# Versa64Cart_v1_5.net
KiCad netlist of a schematic drawn in EAGLE
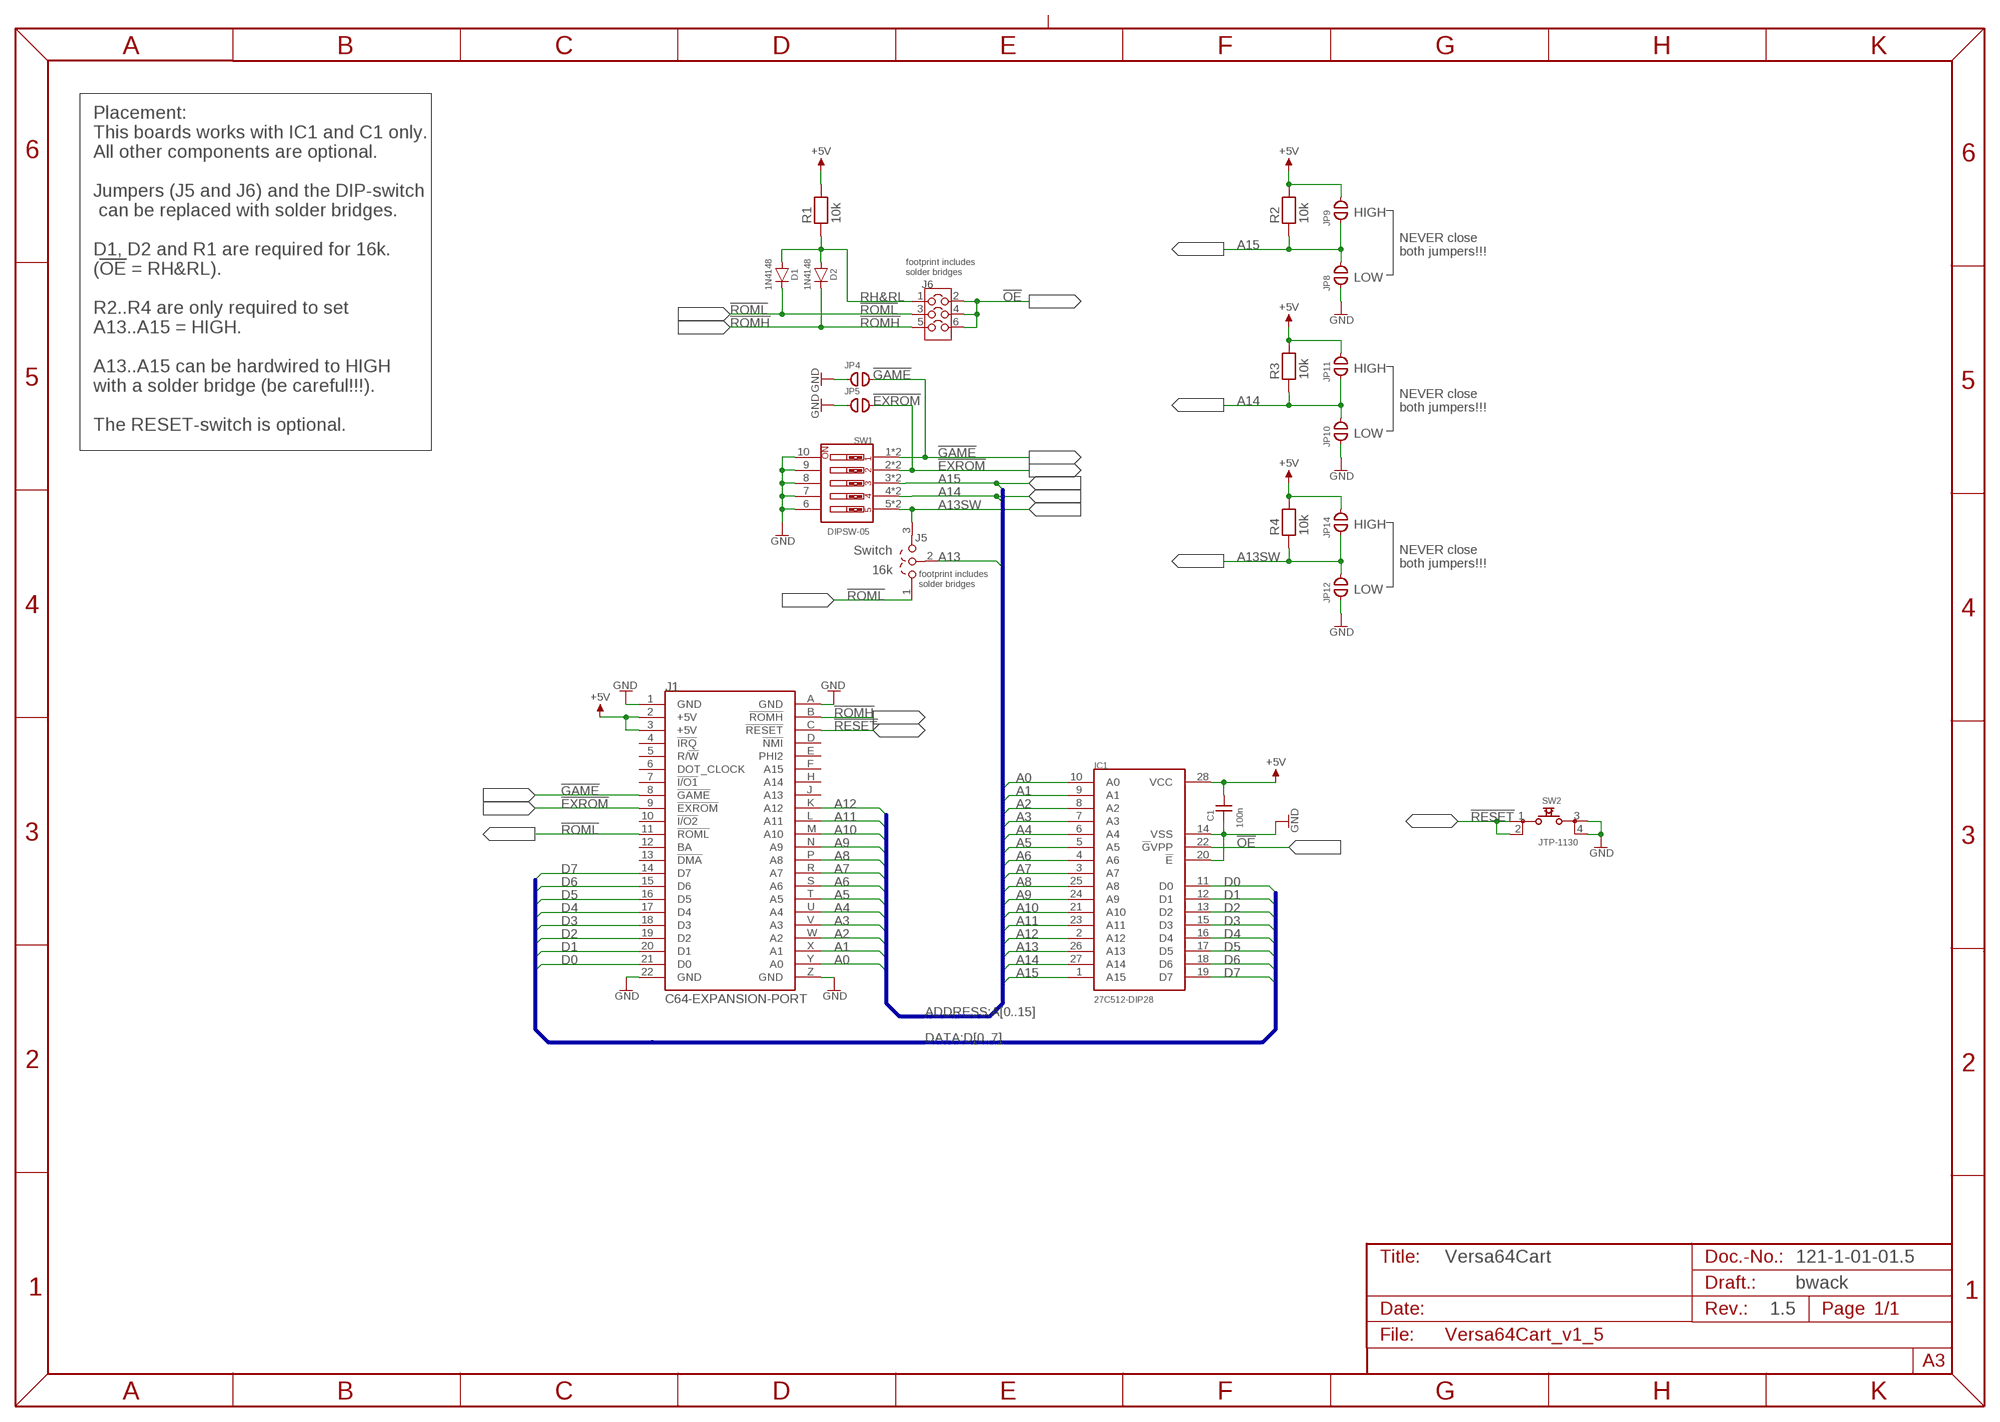
[diagram p0: schematic, sheet 1]

(export (version "E")
  (design (tool "Eeschema 10.0.6"))
  (components
    (comp (ref "C1")
      (value "100n")
      (footprint "eagle-import:C-2,5")
      (libsource (lib "eagle-import") (part "CAP01"))
    )
    (comp (ref "D1")
      (value "1N4148")
      (footprint "eagle-import:DO-35")
      (libsource (lib "eagle-import") (part "1N4148"))
    )
    (comp (ref "D2")
      (value "1N4148")
      (footprint "eagle-import:DO-35")
      (libsource (lib "eagle-import") (part "1N4148"))
    )
    (comp (ref "IC1")
      (value "27C512-DIP28")
      (footprint "eagle-import:DIL28-6")
      (libsource (lib "eagle-import") (part "M27C512-DIP28"))
    )
    (comp (ref "J1")
      (value "C64-EXPANSION-PORT")
      (footprint "eagle-import:EXPANSIO_SQ")
      (libsource (lib "eagle-import") (part "C64-EXPANSIONPNARROW"))
    )
    (comp (ref "J5")
      (value "COMBI-3P")
      (footprint "eagle-import:COMBI-3P")
      (libsource (lib "eagle-import") (part "COMBI-3P"))
    )
    (comp (ref "J6")
      (value "COMBI-3X2P")
      (footprint "eagle-import:COMBI-3X2")
      (fields (field (name "SPICEPREFIX") "X"))
      (libsource (lib "eagle-import") (part "COMBI-3X2P"))
    )
    (comp (ref "JP4")
      (value "OPEN")
      (footprint "eagle-import:CP_OP")
      (libsource (lib "eagle-import") (part "OPEN"))
    )
    (comp (ref "JP5")
      (value "OPEN")
      (footprint "eagle-import:CP_OP")
      (libsource (lib "eagle-import") (part "OPEN"))
    )
    (comp (ref "JP8")
      (value "OPEN")
      (footprint "eagle-import:CP_OP")
      (libsource (lib "eagle-import") (part "OPEN"))
    )
    (comp (ref "JP9")
      (value "OPEN")
      (footprint "eagle-import:CP_OP")
      (libsource (lib "eagle-import") (part "OPEN"))
    )
    (comp (ref "JP10")
      (value "OPEN")
      (footprint "eagle-import:CP_OP")
      (libsource (lib "eagle-import") (part "OPEN"))
    )
    (comp (ref "JP11")
      (value "OPEN")
      (footprint "eagle-import:CP_OP")
      (libsource (lib "eagle-import") (part "OPEN"))
    )
    (comp (ref "JP12")
      (value "OPEN")
      (footprint "eagle-import:CP_OP")
      (libsource (lib "eagle-import") (part "OPEN"))
    )
    (comp (ref "JP14")
      (value "OPEN")
      (footprint "eagle-import:CP_OP")
      (libsource (lib "eagle-import") (part "OPEN"))
    )
    (comp (ref "R1")
      (value "10k")
      (footprint "eagle-import:R-10")
      (libsource (lib "eagle-import") (part "RES04"))
    )
    (comp (ref "R2")
      (value "10k")
      (footprint "eagle-import:R-10")
      (libsource (lib "eagle-import") (part "RES04"))
    )
    (comp (ref "R3")
      (value "10k")
      (footprint "eagle-import:R-10")
      (libsource (lib "eagle-import") (part "RES04"))
    )
    (comp (ref "R4")
      (value "10k")
      (footprint "eagle-import:R-10")
      (libsource (lib "eagle-import") (part "RES04"))
    )
    (comp (ref "SW1")
      (value "DIPSW-05")
      (footprint "eagle-import:DIPSW-05VJ")
      (libsource (lib "eagle-import") (part "DIPSW-05"))
    )
    (comp (ref "SW2")
      (value "JTP-1130")
      (footprint "eagle-import:JTP-1130")
      (libsource (lib "eagle-import") (part "JTP-1130"))
    )
  )
  (nets
    (net (code "25") (name "+5V") (class "Default")
      (node (ref "C1") (pin "2") (pinfunction "2_2") (pintype "passive"))
      (node (ref "IC1") (pin "28") (pinfunction "VCC_28") (pintype "power_in"))
      (node (ref "J1") (pin "2") (pinfunction "+5V_2") (pintype "power_in"))
      (node (ref "J1") (pin "3") (pinfunction "+5V_3") (pintype "power_in"))
      (node (ref "JP11") (pin "2") (pinfunction "2_2") (pintype "passive"))
      (node (ref "JP14") (pin "2") (pinfunction "2_2") (pintype "passive"))
      (node (ref "JP9") (pin "2") (pinfunction "2_2") (pintype "passive"))
      (node (ref "R1") (pin "2") (pinfunction "2_2") (pintype "passive"))
      (node (ref "R2") (pin "2") (pinfunction "2_2") (pintype "passive"))
      (node (ref "R3") (pin "2") (pinfunction "2_2") (pintype "passive"))
      (node (ref "R4") (pin "2") (pinfunction "2_2") (pintype "passive"))
    )
    (net (code "26") (name "/A0") (class "Default")
      (node (ref "IC1") (pin "10") (pinfunction "A0_10") (pintype "input"))
      (node (ref "J1") (pin "Y") (pinfunction "A0_Y") (pintype "bidirectional"))
    )
    (net (code "27") (name "/A1") (class "Default")
      (node (ref "IC1") (pin "9") (pinfunction "A1_9") (pintype "input"))
      (node (ref "J1") (pin "X") (pinfunction "A1_X") (pintype "bidirectional"))
    )
    (net (code "28") (name "/A2") (class "Default")
      (node (ref "IC1") (pin "8") (pinfunction "A2_8") (pintype "input"))
      (node (ref "J1") (pin "W") (pinfunction "A2_W") (pintype "bidirectional"))
    )
    (net (code "29") (name "/A3") (class "Default")
      (node (ref "IC1") (pin "7") (pinfunction "A3_7") (pintype "input"))
      (node (ref "J1") (pin "V") (pinfunction "A3_V") (pintype "bidirectional"))
    )
    (net (code "30") (name "/A4") (class "Default")
      (node (ref "IC1") (pin "6") (pinfunction "A4_6") (pintype "input"))
      (node (ref "J1") (pin "U") (pinfunction "A4_U") (pintype "bidirectional"))
    )
    (net (code "31") (name "/A5") (class "Default")
      (node (ref "IC1") (pin "5") (pinfunction "A5_5") (pintype "input"))
      (node (ref "J1") (pin "T") (pinfunction "A5_T") (pintype "bidirectional"))
    )
    (net (code "32") (name "/A6") (class "Default")
      (node (ref "IC1") (pin "4") (pinfunction "A6_4") (pintype "input"))
      (node (ref "J1") (pin "S") (pinfunction "A6_S") (pintype "bidirectional"))
    )
    (net (code "33") (name "/A7") (class "Default")
      (node (ref "IC1") (pin "3") (pinfunction "A7_3") (pintype "input"))
      (node (ref "J1") (pin "R") (pinfunction "A7_R") (pintype "bidirectional"))
    )
    (net (code "34") (name "/A8") (class "Default")
      (node (ref "IC1") (pin "25") (pinfunction "A8_25") (pintype "input"))
      (node (ref "J1") (pin "P") (pinfunction "A8_P") (pintype "bidirectional"))
    )
    (net (code "35") (name "/A9") (class "Default")
      (node (ref "IC1") (pin "24") (pinfunction "A9_24") (pintype "input"))
      (node (ref "J1") (pin "N") (pinfunction "A9_N") (pintype "bidirectional"))
    )
    (net (code "36") (name "/A10") (class "Default")
      (node (ref "IC1") (pin "21") (pinfunction "A10_21") (pintype "input"))
      (node (ref "J1") (pin "M") (pinfunction "A10_M") (pintype "bidirectional"))
    )
    (net (code "37") (name "/A11") (class "Default")
      (node (ref "IC1") (pin "23") (pinfunction "A11_23") (pintype "input"))
      (node (ref "J1") (pin "L") (pinfunction "A11_L") (pintype "bidirectional"))
    )
    (net (code "38") (name "/A12") (class "Default")
      (node (ref "IC1") (pin "2") (pinfunction "A12_2") (pintype "input"))
      (node (ref "J1") (pin "K") (pinfunction "A12_K") (pintype "bidirectional"))
    )
    (net (code "39") (name "/A13") (class "Default")
      (node (ref "IC1") (pin "26") (pinfunction "A13_26") (pintype "input"))
      (node (ref "J5") (pin "2") (pinfunction "2_2") (pintype "bidirectional"))
    )
    (net (code "40") (name "/A13SW") (class "Default")
      (node (ref "J5") (pin "3") (pinfunction "3_3") (pintype "bidirectional"))
      (node (ref "JP12") (pin "2") (pinfunction "2_2") (pintype "passive"))
      (node (ref "JP14") (pin "1") (pinfunction "1_1") (pintype "passive"))
      (node (ref "R4") (pin "1") (pinfunction "1_1") (pintype "passive"))
      (node (ref "SW1") (pin "5") (pinfunction "5_5") (pintype "passive"))
      (node (ref "SW1") (pin "5J") (pinfunction "5_5J") (pintype "passive"))
    )
    (net (code "41") (name "/A14") (class "Default")
      (node (ref "IC1") (pin "27") (pinfunction "A14_27") (pintype "input"))
      (node (ref "JP10") (pin "2") (pinfunction "2_2") (pintype "passive"))
      (node (ref "JP11") (pin "1") (pinfunction "1_1") (pintype "passive"))
      (node (ref "R3") (pin "1") (pinfunction "1_1") (pintype "passive"))
      (node (ref "SW1") (pin "4") (pinfunction "4_4") (pintype "passive"))
      (node (ref "SW1") (pin "4J") (pinfunction "4_4J") (pintype "passive"))
    )
    (net (code "42") (name "/A15") (class "Default")
      (node (ref "IC1") (pin "1") (pinfunction "A15_1") (pintype "input"))
      (node (ref "JP8") (pin "2") (pinfunction "2_2") (pintype "passive"))
      (node (ref "JP9") (pin "1") (pinfunction "1_1") (pintype "passive"))
      (node (ref "R2") (pin "1") (pinfunction "1_1") (pintype "passive"))
      (node (ref "SW1") (pin "3") (pinfunction "3_3") (pintype "passive"))
      (node (ref "SW1") (pin "3J") (pinfunction "3_3J") (pintype "passive"))
    )
    (net (code "44") (name "/D0") (class "Default")
      (node (ref "IC1") (pin "11") (pinfunction "D0_11") (pintype "bidirectional"))
      (node (ref "J1") (pin "21") (pinfunction "D0_21") (pintype "bidirectional"))
    )
    (net (code "45") (name "/D1") (class "Default")
      (node (ref "IC1") (pin "12") (pinfunction "D1_12") (pintype "bidirectional"))
      (node (ref "J1") (pin "20") (pinfunction "D1_20") (pintype "bidirectional"))
    )
    (net (code "46") (name "/D2") (class "Default")
      (node (ref "IC1") (pin "13") (pinfunction "D2_13") (pintype "bidirectional"))
      (node (ref "J1") (pin "19") (pinfunction "D2_19") (pintype "bidirectional"))
    )
    (net (code "47") (name "/D3") (class "Default")
      (node (ref "IC1") (pin "15") (pinfunction "D3_15") (pintype "bidirectional"))
      (node (ref "J1") (pin "18") (pinfunction "D3_18") (pintype "bidirectional"))
    )
    (net (code "48") (name "/D4") (class "Default")
      (node (ref "IC1") (pin "16") (pinfunction "D4_16") (pintype "bidirectional"))
      (node (ref "J1") (pin "17") (pinfunction "D4_17") (pintype "bidirectional"))
    )
    (net (code "49") (name "/D5") (class "Default")
      (node (ref "IC1") (pin "17") (pinfunction "D5_17") (pintype "bidirectional"))
      (node (ref "J1") (pin "16") (pinfunction "D5_16") (pintype "bidirectional"))
    )
    (net (code "50") (name "/D6") (class "Default")
      (node (ref "IC1") (pin "18") (pinfunction "D6_18") (pintype "bidirectional"))
      (node (ref "J1") (pin "15") (pinfunction "D6_15") (pintype "bidirectional"))
    )
    (net (code "51") (name "/D7") (class "Default")
      (node (ref "IC1") (pin "19") (pinfunction "D7_19") (pintype "bidirectional"))
      (node (ref "J1") (pin "14") (pinfunction "D7_14") (pintype "bidirectional"))
    )
    (net (code "53") (name "/RH&RL") (class "Default")
      (node (ref "D1") (pin "A") (pinfunction "A_A") (pintype "passive"))
      (node (ref "D2") (pin "A") (pinfunction "A_A") (pintype "passive"))
      (node (ref "J6") (pin "1") (pinfunction "1_1") (pintype "bidirectional"))
      (node (ref "R1") (pin "1") (pinfunction "1_1") (pintype "passive"))
    )
    (net (code "54") (name "/~{EXROM}") (class "Default")
      (node (ref "J1") (pin "9") (pinfunction "~{EXROM}_9") (pintype "input"))
      (node (ref "JP5") (pin "2") (pinfunction "2_2") (pintype "passive"))
      (node (ref "SW1") (pin "2") (pinfunction "2_2") (pintype "passive"))
      (node (ref "SW1") (pin "2J") (pinfunction "2_2J") (pintype "passive"))
    )
    (net (code "55") (name "/~{GAME}") (class "Default")
      (node (ref "J1") (pin "8") (pinfunction "~{GAME}_8") (pintype "input"))
      (node (ref "JP4") (pin "2") (pinfunction "2_2") (pintype "passive"))
      (node (ref "SW1") (pin "1") (pinfunction "1_1") (pintype "passive"))
      (node (ref "SW1") (pin "1J") (pinfunction "1_1J") (pintype "passive"))
    )
    (net (code "56") (name "/~{OE}") (class "Default")
      (node (ref "IC1") (pin "22") (pinfunction "~{G}VPP_22") (pintype "input"))
      (node (ref "J6") (pin "2") (pinfunction "2_2") (pintype "bidirectional"))
      (node (ref "J6") (pin "4") (pinfunction "4_4") (pintype "bidirectional"))
      (node (ref "J6") (pin "6") (pinfunction "6_6") (pintype "bidirectional"))
    )
    (net (code "57") (name "/~{RESET}") (class "Default")
      (node (ref "J1") (pin "C") (pinfunction "~{RESET}_C") (pintype "open_collector"))
      (node (ref "SW2") (pin "1") (pinfunction "1_1") (pintype "passive"))
      (node (ref "SW2") (pin "2") (pinfunction "2_2") (pintype "passive"))
    )
    (net (code "58") (name "/~{ROMH}") (class "Default")
      (node (ref "D2") (pin "K") (pinfunction "K_K") (pintype "passive"))
      (node (ref "J1") (pin "B") (pinfunction "~{ROMH}_B") (pintype "output"))
      (node (ref "J6") (pin "5") (pinfunction "5_5") (pintype "bidirectional"))
    )
    (net (code "59") (name "/~{ROML}") (class "Default")
      (node (ref "D1") (pin "K") (pinfunction "K_K") (pintype "passive"))
      (node (ref "J1") (pin "11") (pinfunction "~{ROML}_11") (pintype "output"))
      (node (ref "J5") (pin "1") (pinfunction "1_1") (pintype "bidirectional"))
      (node (ref "J6") (pin "3") (pinfunction "3_3") (pintype "bidirectional"))
    )
    (net (code "60") (name "GND") (class "Default")
      (node (ref "C1") (pin "1") (pinfunction "1_1") (pintype "passive"))
      (node (ref "IC1") (pin "14") (pinfunction "VSS_14") (pintype "power_in"))
      (node (ref "IC1") (pin "20") (pinfunction "~{E}_20") (pintype "input"))
      (node (ref "J1") (pin "1") (pinfunction "GND_1") (pintype "power_in"))
      (node (ref "J1") (pin "22") (pinfunction "GND_22") (pintype "power_in"))
      (node (ref "J1") (pin "A") (pinfunction "GND_A") (pintype "power_in"))
      (node (ref "J1") (pin "Z") (pinfunction "GND_Z") (pintype "power_in"))
      (node (ref "JP10") (pin "1") (pinfunction "1_1") (pintype "passive"))
      (node (ref "JP12") (pin "1") (pinfunction "1_1") (pintype "passive"))
      (node (ref "JP4") (pin "1") (pinfunction "1_1") (pintype "passive"))
      (node (ref "JP5") (pin "1") (pinfunction "1_1") (pintype "passive"))
      (node (ref "JP8") (pin "1") (pinfunction "1_1") (pintype "passive"))
      (node (ref "SW1") (pin "10") (pinfunction "10_10") (pintype "passive"))
      (node (ref "SW1") (pin "6") (pinfunction "6_6") (pintype "passive"))
      (node (ref "SW1") (pin "7") (pinfunction "7_7") (pintype "passive"))
      (node (ref "SW1") (pin "8") (pinfunction "8_8") (pintype "passive"))
      (node (ref "SW1") (pin "9") (pinfunction "9_9") (pintype "passive"))
      (node (ref "SW2") (pin "3") (pinfunction "3_3") (pintype "passive"))
      (node (ref "SW2") (pin "4") (pinfunction "4_4") (pintype "passive"))
    )
    (net (code "61") (name "unconnected-(J1-A13-PadJ)") (class "Default")
      (node (ref "J1") (pin "J") (pinfunction "A13_J") (pintype "bidirectional"))
    )
    (net (code "62") (name "unconnected-(J1-A14-PadH)") (class "Default")
      (node (ref "J1") (pin "H") (pinfunction "A14_H") (pintype "bidirectional"))
    )
    (net (code "63") (name "unconnected-(J1-A15-PadF)") (class "Default")
      (node (ref "J1") (pin "F") (pinfunction "A15_F") (pintype "bidirectional"))
    )
    (net (code "64") (name "unconnected-(J1-BA-Pad12)") (class "Default")
      (node (ref "J1") (pin "12") (pinfunction "BA_12") (pintype "output"))
    )
    (net (code "65") (name "unconnected-(J1-DOT_CLOCK-Pad6)") (class "Default")
      (node (ref "J1") (pin "6") (pinfunction "DOT_CLOCK_6") (pintype "output"))
    )
    (net (code "66") (name "unconnected-(J1-PHI2-PadE)") (class "Default")
      (node (ref "J1") (pin "E") (pinfunction "PHI2_E") (pintype "output"))
    )
    (net (code "67") (name "unconnected-(J1-R{slash}~{W}-Pad5)") (class "Default")
      (node (ref "J1") (pin "5") (pinfunction "R/~{W}_5") (pintype "output"))
    )
    (net (code "68") (name "unconnected-(J1-~{DMA}-Pad13)") (class "Default")
      (node (ref "J1") (pin "13") (pinfunction "~{DMA}_13") (pintype "input"))
    )
    (net (code "69") (name "unconnected-(J1-~{IRQ}-Pad4)") (class "Default")
      (node (ref "J1") (pin "4") (pinfunction "~{IRQ}_4") (pintype "input"))
    )
    (net (code "70") (name "unconnected-(J1-~{I{slash}O1}-Pad7)") (class "Default")
      (node (ref "J1") (pin "7") (pinfunction "~{I/O1}_7") (pintype "output"))
    )
    (net (code "71") (name "unconnected-(J1-~{I{slash}O2}-Pad10)") (class "Default")
      (node (ref "J1") (pin "10") (pinfunction "~{I/O2}_10") (pintype "output"))
    )
    (net (code "72") (name "unconnected-(J1-~{NMI}-PadD)") (class "Default")
      (node (ref "J1") (pin "D") (pinfunction "~{NMI}_D") (pintype "input"))
    )
  )
)
